# battery-charger.net
KiCad netlist of a schematic drawn in EAGLE
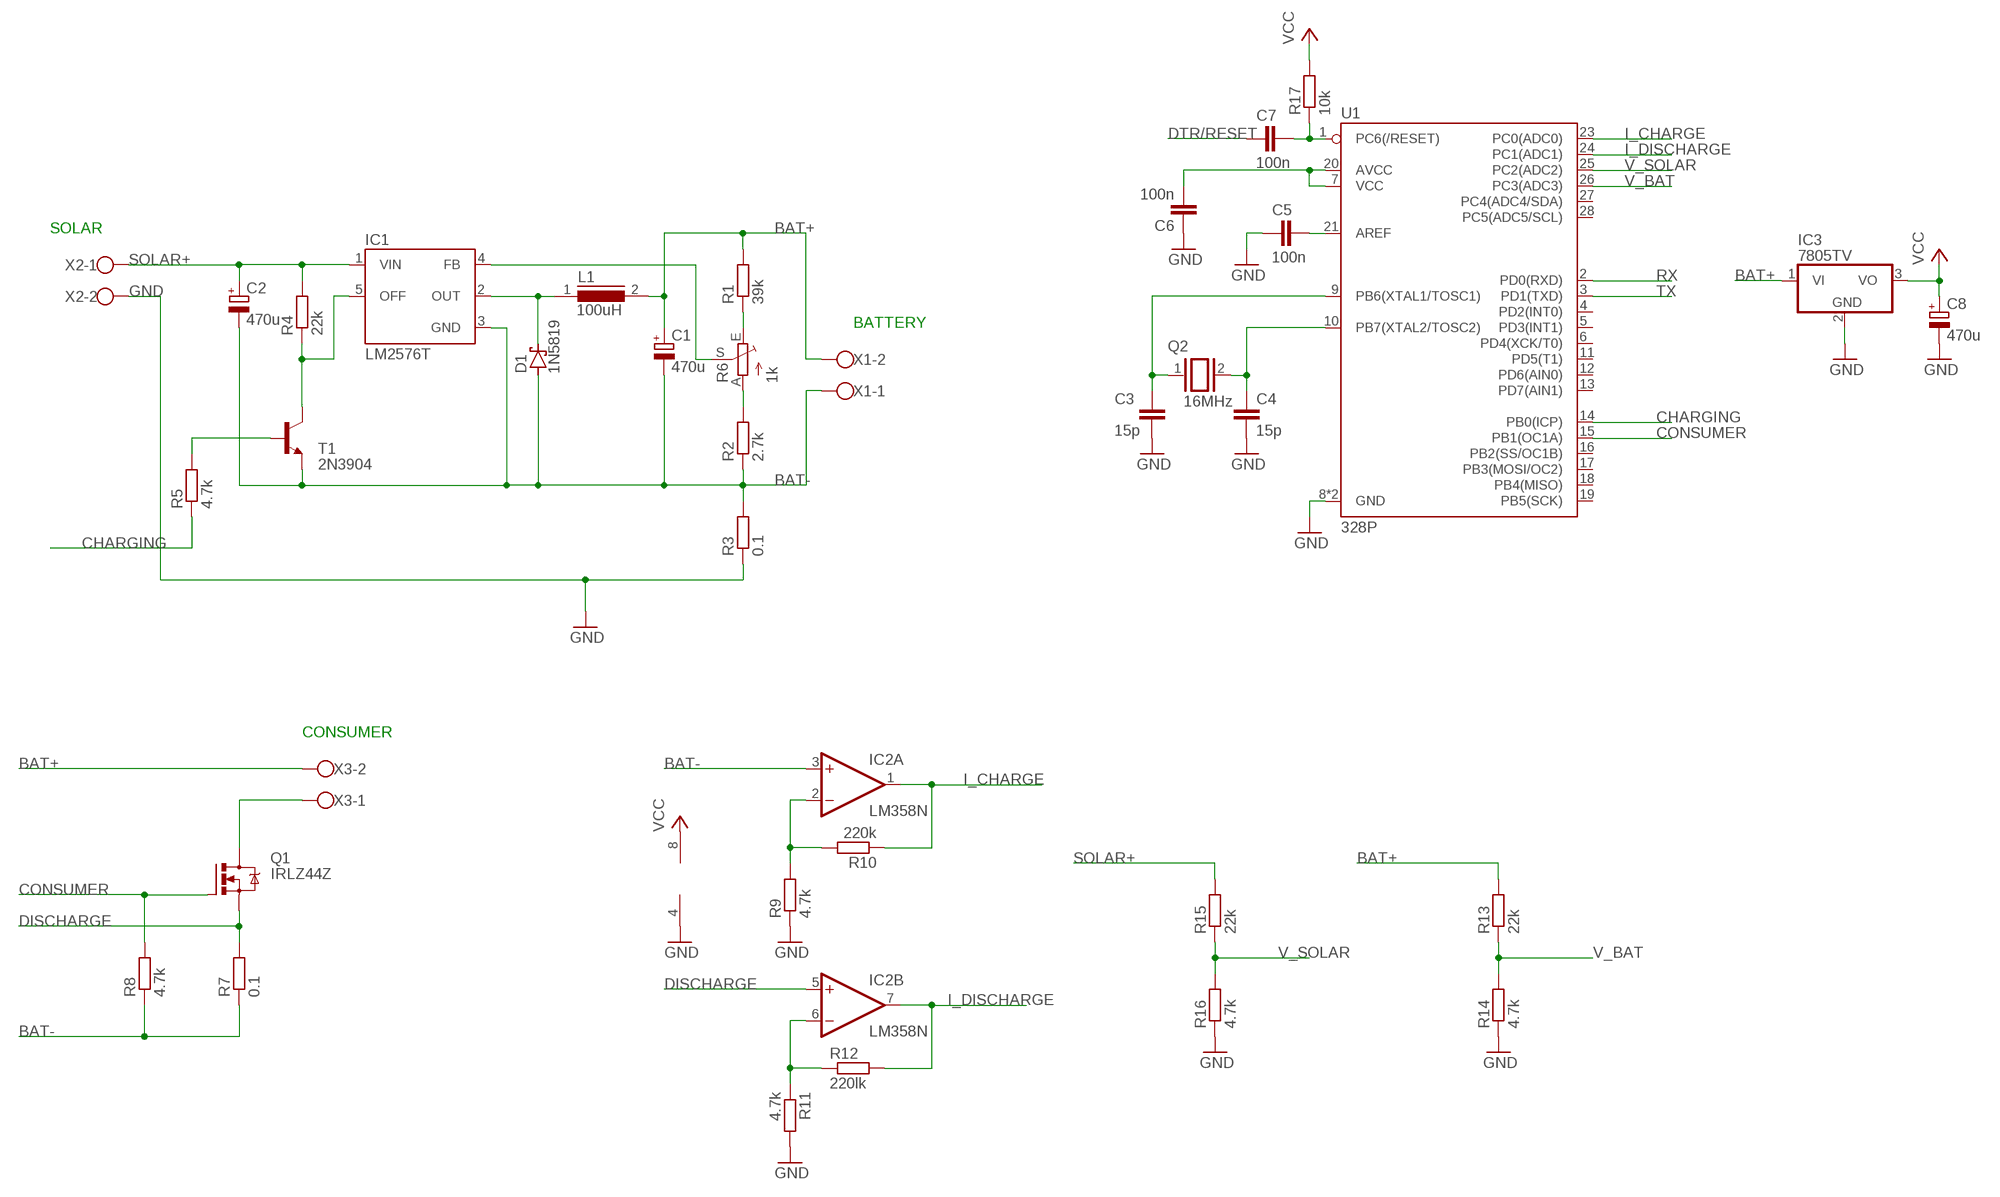
[diagram p0: schematic, sheet 1]

(export (version "E")
  (design (tool "Eeschema 10.0.6"))
  (components
    (comp (ref "C1")
      (value "470u")
      (footprint "eagle-import:E7,5-16")
      (libsource (lib "eagle-import") (part "CPOL-EUE7.5-16"))
    )
    (comp (ref "C2")
      (value "470u")
      (footprint "eagle-import:E7,5-16")
      (libsource (lib "eagle-import") (part "CPOL-EUE7.5-16"))
    )
    (comp (ref "C3")
      (value "15p")
      (footprint "eagle-import:C025-030X050")
      (libsource (lib "eagle-import") (part "C-EU025-030X050"))
    )
    (comp (ref "C4")
      (value "15p")
      (footprint "eagle-import:C025-030X050")
      (libsource (lib "eagle-import") (part "C-EU025-030X050"))
    )
    (comp (ref "C5")
      (value "100n")
      (footprint "eagle-import:C025-030X050")
      (libsource (lib "eagle-import") (part "C-EU025-030X050"))
    )
    (comp (ref "C6")
      (value "100n")
      (footprint "eagle-import:C025-030X050")
      (libsource (lib "eagle-import") (part "C-EU025-030X050"))
    )
    (comp (ref "C7")
      (value "100n")
      (footprint "eagle-import:C025-030X050")
      (libsource (lib "eagle-import") (part "C-EU025-030X050"))
    )
    (comp (ref "C8")
      (value "470u")
      (footprint "eagle-import:E7,5-16")
      (libsource (lib "eagle-import") (part "CPOL-EUE7.5-16"))
    )
    (comp (ref "D1")
      (value "1N5819")
      (footprint "eagle-import:DO41-7.6")
      (libsource (lib "eagle-import") (part "1N5819-T"))
    )
    (comp (ref "IC1")
      (value "LM2576T")
      (footprint "eagle-import:TO220-5")
      (libsource (lib "eagle-import") (part "LM2576T"))
    )
    (comp (ref "IC2")
      (value "LM358N")
      (footprint "eagle-import:DIL08")
      (libsource (lib "eagle-import") (part "LM358N"))
    )
    (comp (ref "IC3")
      (value "7805TV")
      (footprint "eagle-import:TO220V")
      (libsource (lib "eagle-import") (part "78TV05"))
    )
    (comp (ref "L1")
      (value "100uH")
      (footprint "eagle-import:A26GFC")
      (libsource (lib "eagle-import") (part "A26GFC"))
    )
    (comp (ref "Q1")
      (value "IRLZ44Z")
      (footprint "eagle-import:TO220BH")
      (libsource (lib "eagle-import") (part "IRLZ44Z"))
    )
    (comp (ref "Q2")
      (value "16MHz")
      (footprint "eagle-import:QS")
      (libsource (lib "eagle-import") (part "XTAL/S"))
    )
    (comp (ref "R1")
      (value "39k")
      (footprint "eagle-import:0207_10")
      (libsource (lib "eagle-import") (part "R-EU_0207/10"))
    )
    (comp (ref "R2")
      (value "2.7k")
      (footprint "eagle-import:0207_10")
      (libsource (lib "eagle-import") (part "R-EU_0207/10"))
    )
    (comp (ref "R3")
      (value "0.1")
      (footprint "eagle-import:0207_10")
      (libsource (lib "eagle-import") (part "R-EU_0207/10"))
    )
    (comp (ref "R4")
      (value "22k")
      (footprint "eagle-import:0207_10")
      (libsource (lib "eagle-import") (part "R-EU_0207/10"))
    )
    (comp (ref "R5")
      (value "4.7k")
      (footprint "eagle-import:0207_10")
      (libsource (lib "eagle-import") (part "R-EU_0207/10"))
    )
    (comp (ref "R6")
      (value "1k")
      (footprint "eagle-import:RJ9W")
      (libsource (lib "eagle-import") (part "TRIM_EU-RJ9W"))
    )
    (comp (ref "R7")
      (value "0.1")
      (footprint "eagle-import:0207_10")
      (libsource (lib "eagle-import") (part "R-EU_0207/10"))
    )
    (comp (ref "R8")
      (value "4.7k")
      (footprint "eagle-import:0207_10")
      (libsource (lib "eagle-import") (part "R-EU_0207/10"))
    )
    (comp (ref "R9")
      (value "4.7k")
      (footprint "eagle-import:0207_10")
      (libsource (lib "eagle-import") (part "R-EU_0207/10"))
    )
    (comp (ref "R10")
      (value "220k")
      (footprint "eagle-import:0207_10")
      (libsource (lib "eagle-import") (part "R-EU_0207/10"))
    )
    (comp (ref "R11")
      (value "4.7k")
      (footprint "eagle-import:0207_10")
      (libsource (lib "eagle-import") (part "R-EU_0207/10"))
    )
    (comp (ref "R12")
      (value "220lk")
      (footprint "eagle-import:0207_10")
      (libsource (lib "eagle-import") (part "R-EU_0207/10"))
    )
    (comp (ref "R13")
      (value "22k")
      (footprint "eagle-import:0207_10")
      (libsource (lib "eagle-import") (part "R-EU_0207/10"))
    )
    (comp (ref "R14")
      (value "4.7k")
      (footprint "eagle-import:0207_10")
      (libsource (lib "eagle-import") (part "R-EU_0207/10"))
    )
    (comp (ref "R15")
      (value "22k")
      (footprint "eagle-import:0207_10")
      (libsource (lib "eagle-import") (part "R-EU_0207/10"))
    )
    (comp (ref "R16")
      (value "4.7k")
      (footprint "eagle-import:0207_10")
      (libsource (lib "eagle-import") (part "R-EU_0207/10"))
    )
    (comp (ref "R17")
      (value "10k")
      (footprint "eagle-import:0207_10")
      (libsource (lib "eagle-import") (part "R-EU_0207/10"))
    )
    (comp (ref "T1")
      (value "2N3904")
      (footprint "eagle-import:TO92")
      (libsource (lib "eagle-import") (part "2N3904"))
    )
    (comp (ref "U1")
      (value "328P")
      (footprint "eagle-import:DIP28")
      (libsource (lib "eagle-import") (part "ATMEGA328P_PDIP"))
    )
    (comp (ref "X1")
      (value "W237-102")
      (footprint "eagle-import:W237-102")
      (fields (field (name "MPN") "237-102"))
      (libsource (lib "eagle-import") (part "W237-102"))
    )
    (comp (ref "X2")
      (value "W237-102")
      (footprint "eagle-import:W237-102")
      (fields (field (name "MPN") "237-102"))
      (libsource (lib "eagle-import") (part "W237-102"))
    )
    (comp (ref "X3")
      (value "W237-102")
      (footprint "eagle-import:W237-102")
      (fields (field (name "MPN") "237-102"))
      (libsource (lib "eagle-import") (part "W237-102"))
    )
  )
  (nets
    (net (code "1") (name "/BAT+") (class "Default")
      (node (ref "C1") (pin "+") (pinfunction "+_+") (pintype "passive"))
      (node (ref "IC3") (pin "1") (pinfunction "VI_1") (pintype "input"))
      (node (ref "L1") (pin "2") (pinfunction "2_2") (pintype "passive"))
      (node (ref "R1") (pin "2") (pinfunction "2_2") (pintype "passive"))
      (node (ref "R13") (pin "2") (pinfunction "2_2") (pintype "passive"))
      (node (ref "X1") (pin "2") (pinfunction "KL_2") (pintype "passive"))
      (node (ref "X3") (pin "2") (pinfunction "KL_2") (pintype "passive"))
    )
    (net (code "2") (name "/BAT-") (class "Default")
      (node (ref "C1") (pin "-") (pinfunction "-_-") (pintype "passive"))
      (node (ref "C2") (pin "-") (pinfunction "-_-") (pintype "passive"))
      (node (ref "D1") (pin "A") (pinfunction "A_A") (pintype "passive"))
      (node (ref "IC1") (pin "3") (pinfunction "GND_3") (pintype "power_in"))
      (node (ref "IC2") (pin "3") (pinfunction "+IN_3") (pintype "input"))
      (node (ref "R2") (pin "1") (pinfunction "1_1") (pintype "passive"))
      (node (ref "R3") (pin "2") (pinfunction "2_2") (pintype "passive"))
      (node (ref "R7") (pin "1") (pinfunction "1_1") (pintype "passive"))
      (node (ref "R8") (pin "1") (pinfunction "1_1") (pintype "passive"))
      (node (ref "T1") (pin "3") (pinfunction "E_3") (pintype "passive"))
      (node (ref "X1") (pin "1") (pinfunction "KL_1") (pintype "passive"))
    )
    (net (code "3") (name "/CHARGING") (class "Default")
      (node (ref "R5") (pin "1") (pinfunction "1_1") (pintype "passive"))
      (node (ref "U1") (pin "14") (pinfunction "PB0(ICP)_14") (pintype "bidirectional"))
    )
    (net (code "4") (name "/CONSUMER") (class "Default")
      (node (ref "Q1") (pin "G") (pinfunction "G_G") (pintype "passive"))
      (node (ref "R8") (pin "2") (pinfunction "2_2") (pintype "passive"))
      (node (ref "U1") (pin "15") (pinfunction "PB1(OC1A)_15") (pintype "bidirectional"))
    )
    (net (code "5") (name "/DISCHARGE") (class "Default")
      (node (ref "IC2") (pin "5") (pinfunction "+IN_5") (pintype "input"))
      (node (ref "Q1") (pin "S") (pinfunction "S_S") (pintype "passive"))
      (node (ref "R7") (pin "2") (pinfunction "2_2") (pintype "passive"))
    )
    (net (code "6") (name "/DTR{slash}RESET") (class "Default")
      (node (ref "C7") (pin "2") (pinfunction "2_2") (pintype "passive"))
    )
    (net (code "7") (name "/I_CHARGE") (class "Default")
      (node (ref "IC2") (pin "1") (pinfunction "OUT_1") (pintype "output"))
      (node (ref "R10") (pin "1") (pinfunction "1_1") (pintype "passive"))
      (node (ref "U1") (pin "23") (pinfunction "PC0(ADC0)_23") (pintype "bidirectional"))
    )
    (net (code "8") (name "/I_DISCHARGE") (class "Default")
      (node (ref "IC2") (pin "7") (pinfunction "OUT_7") (pintype "output"))
      (node (ref "R12") (pin "2") (pinfunction "2_2") (pintype "passive"))
      (node (ref "U1") (pin "24") (pinfunction "PC1(ADC1)_24") (pintype "bidirectional"))
    )
    (net (code "9") (name "/RX") (class "Default")
      (node (ref "U1") (pin "2") (pinfunction "PD0(RXD)_2") (pintype "bidirectional"))
    )
    (net (code "10") (name "/SOLAR+") (class "Default")
      (node (ref "C2") (pin "+") (pinfunction "+_+") (pintype "passive"))
      (node (ref "IC1") (pin "1") (pinfunction "VIN_1") (pintype "power_in"))
      (node (ref "R15") (pin "2") (pinfunction "2_2") (pintype "passive"))
      (node (ref "R4") (pin "2") (pinfunction "2_2") (pintype "passive"))
      (node (ref "X2") (pin "1") (pinfunction "KL_1") (pintype "passive"))
    )
    (net (code "11") (name "/TX") (class "Default")
      (node (ref "U1") (pin "3") (pinfunction "PD1(TXD)_3") (pintype "bidirectional"))
    )
    (net (code "12") (name "/V_BAT") (class "Default")
      (node (ref "R13") (pin "1") (pinfunction "1_1") (pintype "passive"))
      (node (ref "R14") (pin "2") (pinfunction "2_2") (pintype "passive"))
      (node (ref "U1") (pin "26") (pinfunction "PC3(ADC3)_26") (pintype "bidirectional"))
    )
    (net (code "13") (name "/V_SOLAR") (class "Default")
      (node (ref "R15") (pin "1") (pinfunction "1_1") (pintype "passive"))
      (node (ref "R16") (pin "2") (pinfunction "2_2") (pintype "passive"))
      (node (ref "U1") (pin "25") (pinfunction "PC2(ADC2)_25") (pintype "bidirectional"))
    )
    (net (code "14") (name "GND") (class "Default")
      (node (ref "C3") (pin "2") (pinfunction "2_2") (pintype "passive"))
      (node (ref "C4") (pin "2") (pinfunction "2_2") (pintype "passive"))
      (node (ref "C5") (pin "2") (pinfunction "2_2") (pintype "passive"))
      (node (ref "C6") (pin "1") (pinfunction "1_1") (pintype "passive"))
      (node (ref "C8") (pin "-") (pinfunction "-_-") (pintype "passive"))
      (node (ref "IC2") (pin "4") (pinfunction "V-_4") (pintype "power_in"))
      (node (ref "IC3") (pin "2") (pinfunction "GND_2") (pintype "passive"))
      (node (ref "R11") (pin "2") (pinfunction "2_2") (pintype "passive"))
      (node (ref "R14") (pin "1") (pinfunction "1_1") (pintype "passive"))
      (node (ref "R16") (pin "1") (pinfunction "1_1") (pintype "passive"))
      (node (ref "R3") (pin "1") (pinfunction "1_1") (pintype "passive"))
      (node (ref "R9") (pin "1") (pinfunction "1_1") (pintype "passive"))
      (node (ref "U1") (pin "22") (pinfunction "GND_22") (pintype "bidirectional"))
      (node (ref "U1") (pin "8") (pinfunction "GND_8") (pintype "bidirectional"))
      (node (ref "X2") (pin "2") (pinfunction "KL_2") (pintype "passive"))
    )
    (net (code "15") (name "Net-(IC1-FB)") (class "Default")
      (node (ref "IC1") (pin "4") (pinfunction "FB_4") (pintype "input"))
      (node (ref "R6") (pin "S") (pinfunction "S_S") (pintype "passive"))
    )
    (net (code "16") (name "Net-(IC1-OFF)") (class "Default")
      (node (ref "IC1") (pin "5") (pinfunction "OFF_5") (pintype "input"))
      (node (ref "R4") (pin "1") (pinfunction "1_1") (pintype "passive"))
      (node (ref "T1") (pin "1") (pinfunction "C_1") (pintype "passive"))
    )
    (net (code "17") (name "Net-(IC1-OUT)") (class "Default")
      (node (ref "D1") (pin "C") (pinfunction "C_C") (pintype "passive"))
      (node (ref "IC1") (pin "2") (pinfunction "OUT_2") (pintype "output"))
      (node (ref "L1") (pin "1") (pinfunction "1_1") (pintype "passive"))
    )
    (net (code "18") (name "Net-(IC2A--IN)") (class "Default")
      (node (ref "IC2") (pin "2") (pinfunction "-IN_2") (pintype "input"))
      (node (ref "R10") (pin "2") (pinfunction "2_2") (pintype "passive"))
      (node (ref "R9") (pin "2") (pinfunction "2_2") (pintype "passive"))
    )
    (net (code "19") (name "Net-(IC2B--IN)") (class "Default")
      (node (ref "IC2") (pin "6") (pinfunction "-IN_6") (pintype "input"))
      (node (ref "R11") (pin "1") (pinfunction "1_1") (pintype "passive"))
      (node (ref "R12") (pin "1") (pinfunction "1_1") (pintype "passive"))
    )
    (net (code "20") (name "Net-(R1-Pad1)") (class "Default")
      (node (ref "R1") (pin "1") (pinfunction "1_1") (pintype "passive"))
      (node (ref "R6") (pin "E") (pinfunction "E_E") (pintype "passive"))
    )
    (net (code "21") (name "Net-(R2-Pad2)") (class "Default")
      (node (ref "R2") (pin "2") (pinfunction "2_2") (pintype "passive"))
      (node (ref "R6") (pin "A") (pinfunction "A_A") (pintype "passive"))
    )
    (net (code "22") (name "Net-(T1-B)") (class "Default")
      (node (ref "R5") (pin "2") (pinfunction "2_2") (pintype "passive"))
      (node (ref "T1") (pin "2") (pinfunction "B_2") (pintype "passive"))
    )
    (net (code "23") (name "Net-(U1-AREF)") (class "Default")
      (node (ref "C5") (pin "1") (pinfunction "1_1") (pintype "passive"))
      (node (ref "U1") (pin "21") (pinfunction "AREF_21") (pintype "bidirectional"))
    )
    (net (code "24") (name "Net-(U1-AVCC)") (class "Default")
      (node (ref "C6") (pin "2") (pinfunction "2_2") (pintype "passive"))
      (node (ref "U1") (pin "20") (pinfunction "AVCC_20") (pintype "bidirectional"))
      (node (ref "U1") (pin "7") (pinfunction "VCC_7") (pintype "bidirectional"))
    )
    (net (code "25") (name "Net-(U1-PB6(XTAL1{slash}TOSC1))") (class "Default")
      (node (ref "C3") (pin "1") (pinfunction "1_1") (pintype "passive"))
      (node (ref "Q2") (pin "1") (pinfunction "1_1") (pintype "passive"))
      (node (ref "U1") (pin "9") (pinfunction "PB6(XTAL1/TOSC1)_9") (pintype "bidirectional"))
    )
    (net (code "26") (name "Net-(U1-PB7(XTAL2{slash}TOSC2))") (class "Default")
      (node (ref "C4") (pin "1") (pinfunction "1_1") (pintype "passive"))
      (node (ref "Q2") (pin "2") (pinfunction "2_2") (pintype "passive"))
      (node (ref "U1") (pin "10") (pinfunction "PB7(XTAL2/TOSC2)_10") (pintype "bidirectional"))
    )
    (net (code "27") (name "Net-(U1-PC6({slash}RESET))") (class "Default")
      (node (ref "C7") (pin "1") (pinfunction "1_1") (pintype "passive"))
      (node (ref "R17") (pin "1") (pinfunction "1_1") (pintype "passive"))
      (node (ref "U1") (pin "1") (pinfunction "PC6(/RESET)_1") (pintype "bidirectional"))
    )
    (net (code "28") (name "Net-(X3A-KL)") (class "Default")
      (node (ref "Q1") (pin "D") (pinfunction "D_D") (pintype "passive"))
      (node (ref "X3") (pin "1") (pinfunction "KL_1") (pintype "passive"))
    )
    (net (code "29") (name "VCC") (class "Default")
      (node (ref "C8") (pin "+") (pinfunction "+_+") (pintype "passive"))
      (node (ref "IC2") (pin "8") (pinfunction "V+_8") (pintype "power_in"))
      (node (ref "IC3") (pin "3") (pinfunction "VO_3") (pintype "passive"))
      (node (ref "R17") (pin "2") (pinfunction "2_2") (pintype "passive"))
    )
    (net (code "30") (name "unconnected-(U1-PB2(SS{slash}OC1B)-Pad16)") (class "Default")
      (node (ref "U1") (pin "16") (pinfunction "PB2(SS/OC1B)_16") (pintype "bidirectional"))
    )
    (net (code "31") (name "unconnected-(U1-PB3(MOSI{slash}OC2)-Pad17)") (class "Default")
      (node (ref "U1") (pin "17") (pinfunction "PB3(MOSI/OC2)_17") (pintype "bidirectional"))
    )
    (net (code "32") (name "unconnected-(U1-PB4(MISO)-Pad18)") (class "Default")
      (node (ref "U1") (pin "18") (pinfunction "PB4(MISO)_18") (pintype "bidirectional"))
    )
    (net (code "33") (name "unconnected-(U1-PB5(SCK)-Pad19)") (class "Default")
      (node (ref "U1") (pin "19") (pinfunction "PB5(SCK)_19") (pintype "bidirectional"))
    )
    (net (code "34") (name "unconnected-(U1-PC4(ADC4{slash}SDA)-Pad27)") (class "Default")
      (node (ref "U1") (pin "27") (pinfunction "PC4(ADC4/SDA)_27") (pintype "bidirectional"))
    )
    (net (code "35") (name "unconnected-(U1-PC5(ADC5{slash}SCL)-Pad28)") (class "Default")
      (node (ref "U1") (pin "28") (pinfunction "PC5(ADC5/SCL)_28") (pintype "bidirectional"))
    )
    (net (code "36") (name "unconnected-(U1-PD2(INT0)-Pad4)") (class "Default")
      (node (ref "U1") (pin "4") (pinfunction "PD2(INT0)_4") (pintype "bidirectional"))
    )
    (net (code "37") (name "unconnected-(U1-PD3(INT1)-Pad5)") (class "Default")
      (node (ref "U1") (pin "5") (pinfunction "PD3(INT1)_5") (pintype "bidirectional"))
    )
    (net (code "38") (name "unconnected-(U1-PD4(XCK{slash}T0)-Pad6)") (class "Default")
      (node (ref "U1") (pin "6") (pinfunction "PD4(XCK/T0)_6") (pintype "bidirectional"))
    )
    (net (code "39") (name "unconnected-(U1-PD5(T1)-Pad11)") (class "Default")
      (node (ref "U1") (pin "11") (pinfunction "PD5(T1)_11") (pintype "bidirectional"))
    )
    (net (code "40") (name "unconnected-(U1-PD6(AIN0)-Pad12)") (class "Default")
      (node (ref "U1") (pin "12") (pinfunction "PD6(AIN0)_12") (pintype "bidirectional"))
    )
    (net (code "41") (name "unconnected-(U1-PD7(AIN1)-Pad13)") (class "Default")
      (node (ref "U1") (pin "13") (pinfunction "PD7(AIN1)_13") (pintype "bidirectional"))
    )
  )
)
